# Amplifier.net
KiCad netlist of a schematic drawn in Altium Designer
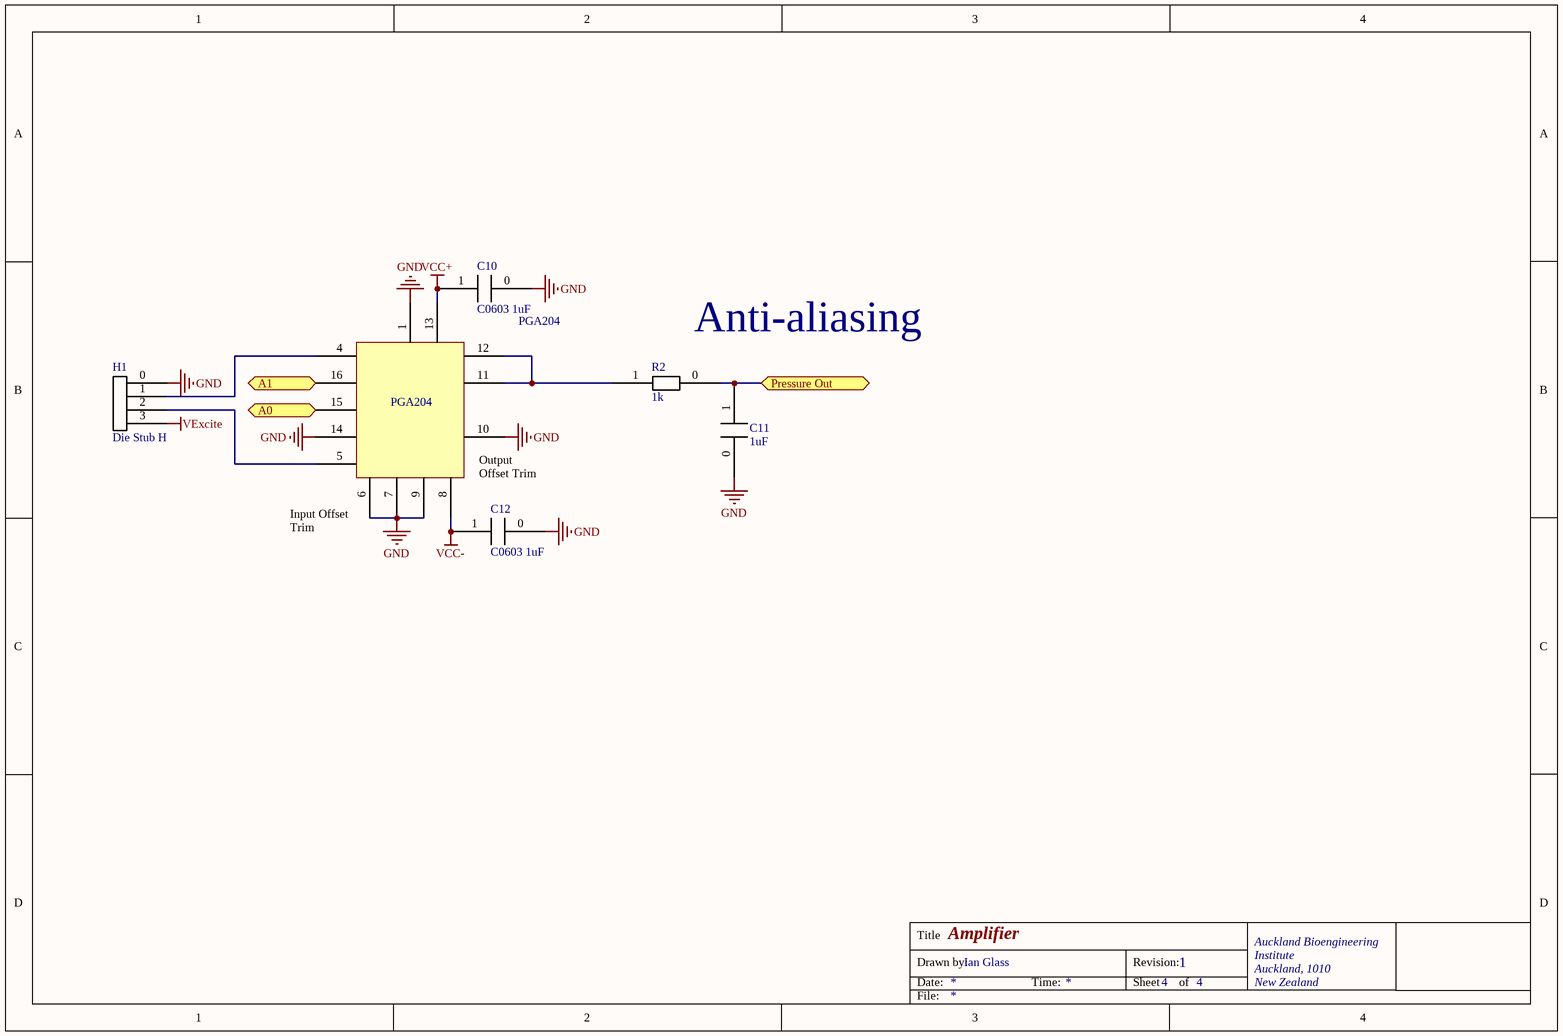
[diagram p0: Amplifier.SchDoc]

(export (version "E")
  (design (tool "Eeschema 10.0.6"))
  (components
    (comp (ref "C10")
      (value "C0603 1uF")
      (footprint "PcbLib1:C0603 1uF")
      (libsource (lib "Schlib1") (part "C0603 1uF"))
    )
    (comp (ref "C11")
      (value "1uF")
      (footprint "PcbLib1:C0603 1uF")
      (libsource (lib "Schlib1") (part "C0603 1uF"))
    )
    (comp (ref "C12")
      (value "C0603 1uF")
      (footprint "PcbLib1:C0603 1uF")
      (libsource (lib "Schlib1") (part "C0603 1uF"))
    )
    (comp (ref "H1")
      (value "Die Stub H")
      (footprint "PcbLib1:Header1x4")
      (libsource (lib "Schlib1") (part "Header1x4"))
    )
    (comp (ref "PGA204")
      (value "PGA204")
      (footprint "PcbLib1:PGA204")
      (libsource (lib "Schlib1") (part "PGA204"))
    )
    (comp (ref "R2")
      (value "1k")
      (footprint "PcbLib1:RT0603 330k")
      (libsource (lib "Schlib1") (part "RT0603 330k"))
    )
  )
  (nets
    (net (code "1") (name "/A0") (class "Default")
      (node (ref "PGA204") (pin "15") (pinfunction "15_15") (pintype "passive"))
    )
    (net (code "2") (name "/A1") (class "Default")
      (node (ref "PGA204") (pin "16") (pinfunction "16_16") (pintype "passive"))
    )
    (net (code "3") (name "/Pressure Out") (class "Default")
      (node (ref "C11") (pin "1") (pinfunction "1_1") (pintype "passive"))
      (node (ref "R2") (pin "0") (pinfunction "0_0") (pintype "passive"))
    )
    (net (code "4") (name "GND") (class "Default")
      (node (ref "C10") (pin "0") (pinfunction "0_0") (pintype "passive"))
      (node (ref "C11") (pin "0") (pinfunction "0_0") (pintype "passive"))
      (node (ref "C12") (pin "0") (pinfunction "0_0") (pintype "passive"))
      (node (ref "H1") (pin "0") (pinfunction "0_0") (pintype "passive"))
      (node (ref "PGA204") (pin "1") (pinfunction "1_1") (pintype "passive"))
      (node (ref "PGA204") (pin "10") (pinfunction "10_10") (pintype "passive"))
      (node (ref "PGA204") (pin "14") (pinfunction "14_14") (pintype "passive"))
      (node (ref "PGA204") (pin "6") (pinfunction "6_6") (pintype "passive"))
      (node (ref "PGA204") (pin "7") (pinfunction "7_7") (pintype "passive"))
      (node (ref "PGA204") (pin "9") (pinfunction "9_9") (pintype "passive"))
    )
    (net (code "5") (name "Net-(H1-Pad1)") (class "Default")
      (node (ref "H1") (pin "1") (pinfunction "1_1") (pintype "passive"))
      (node (ref "PGA204") (pin "4") (pinfunction "4_4") (pintype "passive"))
    )
    (net (code "6") (name "Net-(H1-Pad2)") (class "Default")
      (node (ref "H1") (pin "2") (pinfunction "2_2") (pintype "passive"))
      (node (ref "PGA204") (pin "5") (pinfunction "5_5") (pintype "passive"))
    )
    (net (code "7") (name "Net-(PGA204-Pad11)") (class "Default")
      (node (ref "PGA204") (pin "11") (pinfunction "11_11") (pintype "passive"))
      (node (ref "PGA204") (pin "12") (pinfunction "12_12") (pintype "passive"))
      (node (ref "R2") (pin "1") (pinfunction "1_1") (pintype "passive"))
    )
    (net (code "8") (name "VCC+") (class "Default")
      (node (ref "C10") (pin "1") (pinfunction "1_1") (pintype "passive"))
      (node (ref "PGA204") (pin "13") (pinfunction "13_13") (pintype "passive"))
    )
    (net (code "9") (name "VCC-") (class "Default")
      (node (ref "C12") (pin "1") (pinfunction "1_1") (pintype "passive"))
      (node (ref "PGA204") (pin "8") (pinfunction "8_8") (pintype "passive"))
    )
    (net (code "10") (name "VExcite") (class "Default")
      (node (ref "H1") (pin "3") (pinfunction "3_3") (pintype "passive"))
    )
  )
)
